# 03_-_Power_NDP_BLE_and_LRA.net
KiCad netlist of a schematic drawn in Altium Designer
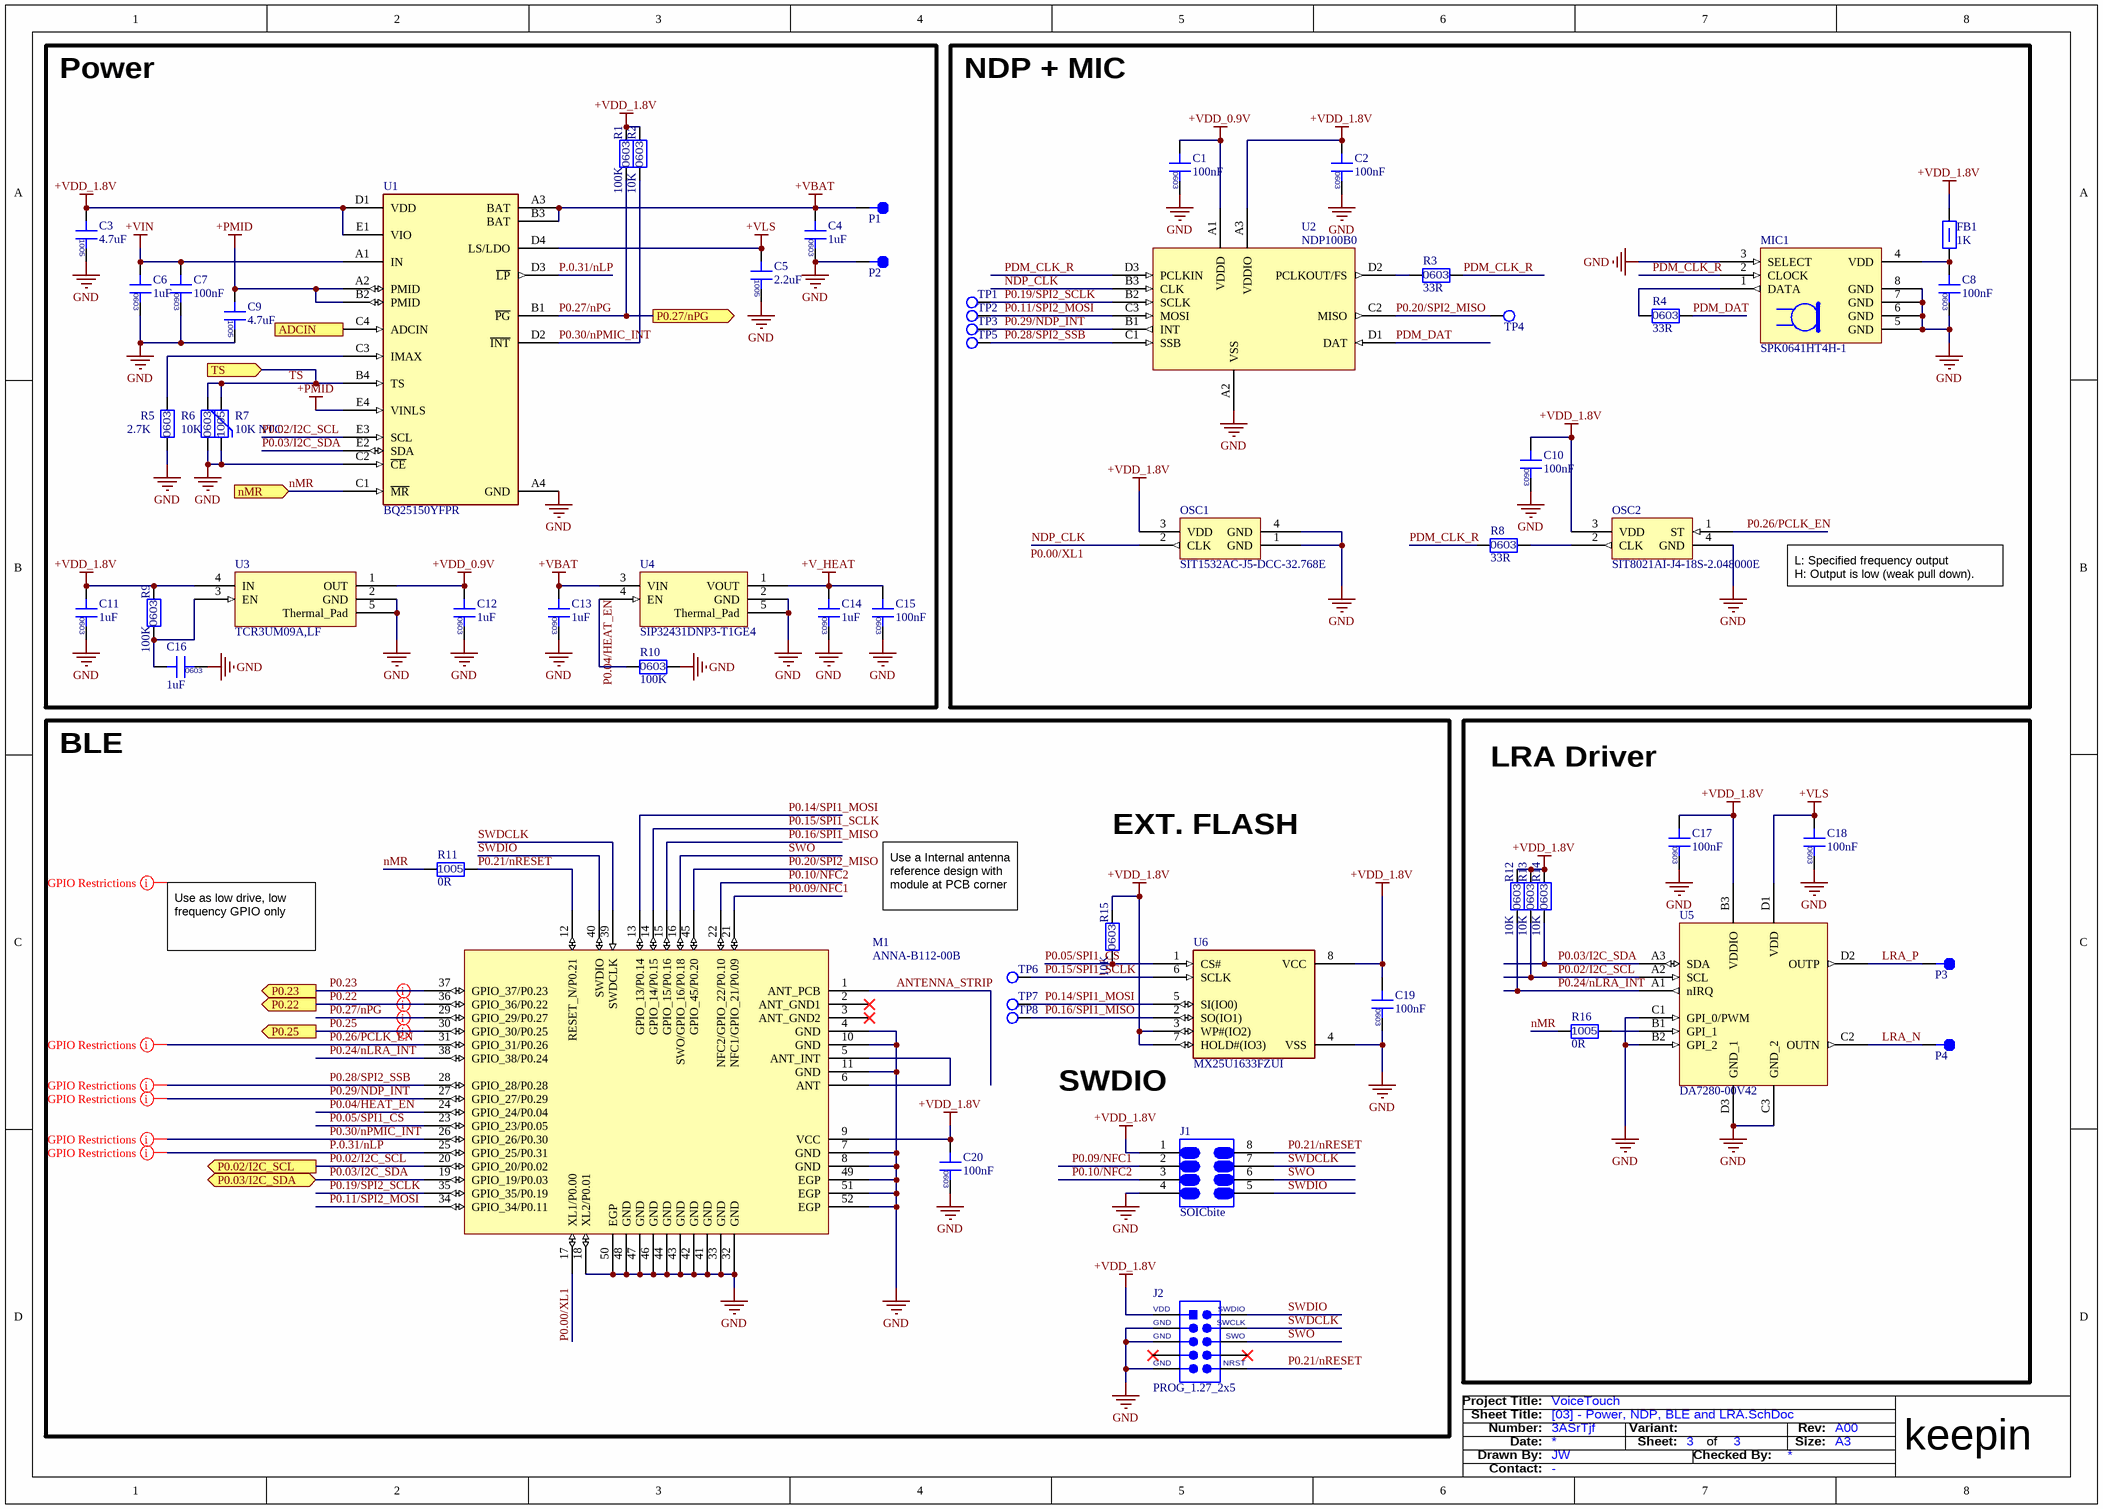
[diagram p0: [03] - Power, NDP, BLE and LRA.SchDoc]

(export (version "E")
  (design (tool "Eeschema 10.0.6"))
  (components
    (comp (ref "C1")
      (value "100nF")
      (footprint "CAPC0603X03N")
      (description "CAP CER 0.1UF 16V X7S 0201")
      (fields
        (field (name "MANUFACTURER") "Murata")
        (field (name "MANUFACTURER PART NUMBER") "GRM033C71C104ME14D")
      )
      (libsource (lib "Schlib-master") (part "GRM033C71C104ME14D"))
    )
    (comp (ref "C2")
      (value "100nF")
      (footprint "CAPC0603X03N")
      (description "CAP CER 0.1UF 16V X7S 0201")
      (fields
        (field (name "MANUFACTURER") "Murata")
        (field (name "MANUFACTURER PART NUMBER") "GRM033C71C104ME14D")
      )
      (libsource (lib "Schlib-master") (part "GRM033C71C104ME14D"))
    )
    (comp (ref "C3")
      (value "4.7uF")
      (footprint "CAPC1005X06N")
      (description "CAP CER 4.7UF 16V X5R 0402")
      (fields (field (name "TOLERANCE") "20%") (field (name "MANUFACTURER") "Samsung"))
      (libsource (lib "Schlib-master") (part "CL05A475MO5NUNC"))
    )
    (comp (ref "C4")
      (value "1uF")
      (footprint "CAPC0603X03N")
      (description "CAP CER 1UF 16V X5R 0201")
      (fields
        (field (name "MANUFACTURER") "Samsung")
        (field (name "MANUFACTURER PART NUMBER") "CL03A105MO3NRNH")
      )
      (libsource (lib "Schlib-master") (part "CL03A105MO3NRNH"))
    )
    (comp (ref "C5")
      (value "2.2uF")
      (footprint "CAPC1005X06N")
      (description "CAP CER 2.2UF 10V X5R 0402")
      (fields
        (field (name "MANUFACTURER") "Samsung")
        (field (name "MANUFACTURER PART NUMBER") "CL05A225KP7NSB8")
      )
      (libsource (lib "Schlib-master") (part "CL05A225KP7NSB8"))
    )
    (comp (ref "C6")
      (value "1uF")
      (footprint "CAPC0603X03N")
      (description "CAP CER 1UF 16V X5R 0201")
      (fields
        (field (name "MANUFACTURER") "Samsung")
        (field (name "MANUFACTURER PART NUMBER") "CL03A105MO3NRNH")
      )
      (libsource (lib "Schlib-master") (part "CL03A105MO3NRNH"))
    )
    (comp (ref "C7")
      (value "100nF")
      (footprint "CAPC0603X03N")
      (description "CAP CER 0.1UF 16V X7S 0201")
      (fields
        (field (name "MANUFACTURER") "Murata")
        (field (name "MANUFACTURER PART NUMBER") "GRM033C71C104ME14D")
      )
      (libsource (lib "Schlib-master") (part "GRM033C71C104ME14D"))
    )
    (comp (ref "C8")
      (value "100nF")
      (footprint "CAPC0603X03N")
      (description "CAP CER 0.1UF 16V X7S 0201")
      (fields
        (field (name "MANUFACTURER") "Murata")
        (field (name "MANUFACTURER PART NUMBER") "GRM033C71C104ME14D")
      )
      (libsource (lib "Schlib-master") (part "GRM033C71C104ME14D"))
    )
    (comp (ref "C9")
      (value "4.7uF")
      (footprint "CAPC1005X06N")
      (description "CAP CER 4.7UF 16V X5R 0402")
      (fields (field (name "TOLERANCE") "20%") (field (name "MANUFACTURER") "Samsung"))
      (libsource (lib "Schlib-master") (part "CL05A475MO5NUNC"))
    )
    (comp (ref "C10")
      (value "100nF")
      (footprint "CAPC0603X03N")
      (description "CAP CER 0.1UF 16V X7S 0201")
      (fields
        (field (name "MANUFACTURER") "Murata")
        (field (name "MANUFACTURER PART NUMBER") "GRM033C71C104ME14D")
      )
      (libsource (lib "Schlib-master") (part "GRM033C71C104ME14D"))
    )
    (comp (ref "C11")
      (value "1uF")
      (footprint "CAPC0603X03N")
      (description "CAP CER 1UF 16V X5R 0201")
      (fields
        (field (name "MANUFACTURER") "Samsung")
        (field (name "MANUFACTURER PART NUMBER") "CL03A105MO3NRNH")
      )
      (libsource (lib "Schlib-master") (part "CL03A105MO3NRNH"))
    )
    (comp (ref "C12")
      (value "1uF")
      (footprint "CAPC0603X03N")
      (description "CAP CER 1UF 16V X5R 0201")
      (fields
        (field (name "MANUFACTURER") "Samsung")
        (field (name "MANUFACTURER PART NUMBER") "CL03A105MO3NRNH")
      )
      (libsource (lib "Schlib-master") (part "CL03A105MO3NRNH"))
    )
    (comp (ref "C13")
      (value "1uF")
      (footprint "CAPC0603X03N")
      (description "CAP CER 1UF 16V X5R 0201")
      (fields
        (field (name "MANUFACTURER") "Samsung")
        (field (name "MANUFACTURER PART NUMBER") "CL03A105MO3NRNH")
      )
      (libsource (lib "Schlib-master") (part "CL03A105MO3NRNH"))
    )
    (comp (ref "C14")
      (value "1uF")
      (footprint "CAPC0603X03N")
      (description "CAP CER 1UF 16V X5R 0201")
      (fields
        (field (name "MANUFACTURER") "Samsung")
        (field (name "MANUFACTURER PART NUMBER") "CL03A105MO3NRNH")
      )
      (libsource (lib "Schlib-master") (part "CL03A105MO3NRNH"))
    )
    (comp (ref "C15")
      (value "100nF")
      (footprint "CAPC0603X03N")
      (description "CAP CER 0.1UF 16V X7S 0201")
      (fields
        (field (name "MANUFACTURER") "Murata")
        (field (name "MANUFACTURER PART NUMBER") "GRM033C71C104ME14D")
      )
      (libsource (lib "Schlib-master") (part "GRM033C71C104ME14D"))
    )
    (comp (ref "C16")
      (value "1uF")
      (footprint "CAPC0603X03N")
      (description "CAP CER 1UF 16V X5R 0201")
      (fields
        (field (name "MANUFACTURER") "Samsung")
        (field (name "MANUFACTURER PART NUMBER") "CL03A105MO3NRNH")
      )
      (libsource (lib "Schlib-master") (part "CL03A105MO3NRNH"))
    )
    (comp (ref "C17")
      (value "100nF")
      (footprint "CAPC0603X03N")
      (description "CAP CER 0.1UF 16V X7S 0201")
      (fields
        (field (name "MANUFACTURER") "Murata")
        (field (name "MANUFACTURER PART NUMBER") "GRM033C71C104ME14D")
      )
      (libsource (lib "Schlib-master") (part "GRM033C71C104ME14D"))
    )
    (comp (ref "C18")
      (value "100nF")
      (footprint "CAPC0603X03N")
      (description "CAP CER 0.1UF 16V X7S 0201")
      (fields
        (field (name "MANUFACTURER") "Murata")
        (field (name "MANUFACTURER PART NUMBER") "GRM033C71C104ME14D")
      )
      (libsource (lib "Schlib-master") (part "GRM033C71C104ME14D"))
    )
    (comp (ref "C19")
      (value "100nF")
      (footprint "CAPC0603X03N")
      (description "CAP CER 0.1UF 16V X7S 0201")
      (fields
        (field (name "MANUFACTURER") "Murata")
        (field (name "MANUFACTURER PART NUMBER") "GRM033C71C104ME14D")
      )
      (libsource (lib "Schlib-master") (part "GRM033C71C104ME14D"))
    )
    (comp (ref "C20")
      (value "100nF")
      (footprint "CAPC0603X03N")
      (description "CAP CER 0.1UF 16V X7S 0201")
      (fields
        (field (name "MANUFACTURER") "Murata")
        (field (name "MANUFACTURER PART NUMBER") "GRM033C71C104ME14D")
      )
      (libsource (lib "Schlib-master") (part "GRM033C71C104ME14D"))
    )
    (comp (ref "FB1")
      (value "1K")
      (footprint "INDC1005X05N")
      (description "FERRITE BEAD 1 KOHM 0402 1LN")
      (fields (field (name "TOLERANCE") "25%") (field (name "MANUFACTURER") "Murata"))
      (libsource (lib "Schlib") (part "BLM15HG102SN1D"))
    )
    (comp (ref "J1")
      (value "SOICbite")
      (footprint "SOICBITE")
      (fields (field (name "MANUFACTURER") "SimonMerrett"))
      (libsource (lib "Schlib-master") (part "SOICbite"))
    )
    (comp (ref "J2")
      (value "PROG_1.27_2x5")
      (footprint "2x5_HEADER_1.27_SMD")
      (description "CONN HEADER SMD 10POS 1.27MM")
      (fields
        (field (name "MANUFACTURER") "Amphenol FCI")
        (field (name "MANUFACTURER PART NUMBER") "20021121-00010C4LF")
      )
      (libsource (lib "Schlib-master") (part "PROG_1.27_2x5"))
    )
    (comp (ref "M1")
      (value "ANNA-B112-00B")
      (footprint "ANNA-B112")
      (description "RX TXRX MODULE BLUETOOTH SMD")
      (fields (field (name "MANUFACTURER") "u-blox"))
      (libsource (lib "Schlib-master") (part "ANNA-B112-00B"))
    )
    (comp (ref "MIC1")
      (value "SPK0641HT4H-1")
      (footprint "MIC_SPK0838HT4H-1")
      (description "RAMIS MIC MULTIMODE DGT TOP PORT")
      (fields (field (name "MANUFACTURER") "Knowles"))
      (libsource (lib "Schlib") (part "SPK0641HT4H-1"))
    )
    (comp (ref "OSC1")
      (value "SIT1532AC-J5-DCC-32.768E")
      (footprint "SIT1532")
      (description "MEMS OSC XO 32.7680KHZ LVCMOS")
      (fields (field (name "MANUFACTURER") "SiTime"))
      (libsource (lib "Schlib-master") (part "SIT1532AC-J5-DCC-32.768E"))
    )
    (comp (ref "OSC2")
      (value "SIT8021AI-J4-18S-2.048000E")
      (footprint "SIT1532")
      (description "MEMS OSC XO 2.0480MHZ LVCMOS SMD")
      (fields (field (name "MANUFACTURER") "SiTime"))
      (libsource (lib "Schlib-master") (part "SIT8021AI-J4-18S-2.048000E"))
    )
    (comp (ref "P1")
      (value "1x1_Octagonal_1.27")
      (footprint "1x1_OCTAGONAL_1.27")
      (libsource (lib "Schlib-master") (part "1x1_Octagonal_1.27"))
    )
    (comp (ref "P2")
      (value "1x1_Octagonal_1.27")
      (footprint "1x1_OCTAGONAL_1.27")
      (libsource (lib "Schlib-master") (part "1x1_Octagonal_1.27"))
    )
    (comp (ref "P3")
      (value "1x1_Octagonal_1.27")
      (footprint "1x1_OCTAGONAL_1.27")
      (libsource (lib "Schlib-master") (part "1x1_Octagonal_1.27"))
    )
    (comp (ref "P4")
      (value "1x1_Octagonal_1.27")
      (footprint "1x1_OCTAGONAL_1.27")
      (libsource (lib "Schlib-master") (part "1x1_Octagonal_1.27"))
    )
    (comp (ref "R1")
      (value "100K")
      (footprint "RESC0603X02N")
      (description "RES SMD 100K OHM 5% 1/20W 0201")
      (fields
        (field (name "MANUFACTURER") "Yageo")
        (field (name "MANUFACTURER PART NUMBER") "RC0201JR-07100KL")
      )
      (libsource (lib "Schlib-master") (part "RC0201JR-07100KL"))
    )
    (comp (ref "R2")
      (value "10K")
      (footprint "RESC0603X02N")
      (description "RES SMD 10K OHM 1% 1/20W 0201")
      (fields
        (field (name "MANUFACTURER") "Yageo")
        (field (name "MANUFACTURER PART NUMBER") "RC0201FR-0710KL")
      )
      (libsource (lib "Schlib-master") (part "RC0201FR-0710KL"))
    )
    (comp (ref "R3")
      (value "33R")
      (footprint "RESC0603X02N")
      (description "RES SMD 33 OHM 1% 1/20W 0201")
      (fields
        (field (name "MANUFACTURER") "Yageo")
        (field (name "MANUFACTURER PART NUMBER") "RC0201FR-0733RL")
      )
      (libsource (lib "Schlib-master") (part "RC0201FR-0733RL"))
    )
    (comp (ref "R4")
      (value "33R")
      (footprint "RESC0603X02N")
      (description "RES SMD 33 OHM 1% 1/20W 0201")
      (fields
        (field (name "MANUFACTURER") "Yageo")
        (field (name "MANUFACTURER PART NUMBER") "RC0201FR-0733RL")
      )
      (libsource (lib "Schlib-master") (part "RC0201FR-0733RL"))
    )
    (comp (ref "R5")
      (value "2.7K")
      (footprint "RESC0603X02N")
      (description "RES SMD 2.7K OHM 1% 1/20W 0201")
      (fields
        (field (name "MANUFACTURER") "Yageo")
        (field (name "MANUFACTURER PART NUMBER") "RC0201FR-072K7L")
      )
      (libsource (lib "Schlib-master") (part "RC0201FR-072K7L"))
    )
    (comp (ref "R6")
      (value "10K")
      (footprint "RESC0603X02N")
      (description "RES SMD 10K OHM 1% 1/20W 0201")
      (fields
        (field (name "MANUFACTURER") "Yageo")
        (field (name "MANUFACTURER PART NUMBER") "RC0201FR-0710KL")
      )
      (libsource (lib "Schlib-master") (part "RC0201FR-0710KL"))
    )
    (comp (ref "R7")
      (value "10K NTC")
      (footprint "NTC1005X05N")
      (description "THERMISTOR NTC 10KOHM 3380K 0402")
      (fields (field (name "TOLERANCE") "5%") (field (name "MANUFACTURER") "Murata"))
      (libsource (lib "Schlib-master") (part "NCP15XH103J03RC"))
    )
    (comp (ref "R8")
      (value "33R")
      (footprint "RESC0603X02N")
      (description "RES SMD 33 OHM 1% 1/20W 0201")
      (fields
        (field (name "MANUFACTURER") "Yageo")
        (field (name "MANUFACTURER PART NUMBER") "RC0201FR-0733RL")
      )
      (libsource (lib "Schlib-master") (part "RC0201FR-0733RL"))
    )
    (comp (ref "R9")
      (value "100K")
      (footprint "RESC0603X02N")
      (description "RES SMD 100K OHM 5% 1/20W 0201")
      (fields
        (field (name "MANUFACTURER") "Yageo")
        (field (name "MANUFACTURER PART NUMBER") "RC0201JR-07100KL")
      )
      (libsource (lib "Schlib-master") (part "RC0201JR-07100KL"))
    )
    (comp (ref "R10")
      (value "100K")
      (footprint "RESC0603X02N")
      (description "RES SMD 100K OHM 5% 1/20W 0201")
      (fields
        (field (name "MANUFACTURER") "Yageo")
        (field (name "MANUFACTURER PART NUMBER") "RC0201JR-07100KL")
      )
      (libsource (lib "") (part "RC0201JR-07100KL_1"))
    )
    (comp (ref "R11")
      (value "0R")
      (footprint "RESC1005X04N")
      (description "RES SMD 0 OHM JUMPER 1/16W 0402")
      (fields
        (field (name "MANUFACTURER") "Yageo")
        (field (name "MANUFACTURER PART NUMBER") "RC0402JR-070RL")
      )
      (libsource (lib "Schlib-master") (part "RC0402JR-070RL"))
    )
    (comp (ref "R12")
      (value "10K")
      (footprint "RESC0603X02N")
      (description "RES SMD 10K OHM 1% 1/20W 0201")
      (fields
        (field (name "MANUFACTURER") "Yageo")
        (field (name "MANUFACTURER PART NUMBER") "RC0201FR-0710KL")
      )
      (libsource (lib "Schlib-master") (part "RC0201FR-0710KL"))
    )
    (comp (ref "R13")
      (value "10K")
      (footprint "RESC0603X02N")
      (description "RES SMD 10K OHM 1% 1/20W 0201")
      (fields
        (field (name "MANUFACTURER") "Yageo")
        (field (name "MANUFACTURER PART NUMBER") "RC0201FR-0710KL")
      )
      (libsource (lib "Schlib-master") (part "RC0201FR-0710KL"))
    )
    (comp (ref "R14")
      (value "10K")
      (footprint "RESC0603X02N")
      (description "RES SMD 10K OHM 1% 1/20W 0201")
      (fields
        (field (name "MANUFACTURER") "Yageo")
        (field (name "MANUFACTURER PART NUMBER") "RC0201FR-0710KL")
      )
      (libsource (lib "Schlib-master") (part "RC0201FR-0710KL"))
    )
    (comp (ref "R15")
      (value "10K")
      (footprint "RESC0603X02N")
      (description "RES SMD 10K OHM 1% 1/20W 0201")
      (fields
        (field (name "MANUFACTURER") "Yageo")
        (field (name "MANUFACTURER PART NUMBER") "RC0201FR-0710KL")
      )
      (libsource (lib "Schlib-master") (part "RC0201FR-0710KL"))
    )
    (comp (ref "R16")
      (value "0R")
      (footprint "RESC1005X04N")
      (description "RES SMD 0 OHM JUMPER 1/16W 0402")
      (fields
        (field (name "MANUFACTURER") "Yageo")
        (field (name "MANUFACTURER PART NUMBER") "RC0402JR-070RL")
      )
      (libsource (lib "Schlib-master") (part "RC0402JR-070RL"))
    )
    (comp (ref "TP1")
      (value "TESTPOINT")
      (footprint "TESTPOINT_0.5mm")
      (description "TESTPOINT PAD")
      (libsource (lib "Schlib-master") (part "TESTPOINT"))
    )
    (comp (ref "TP2")
      (value "TESTPOINT")
      (footprint "TESTPOINT_0.5mm")
      (description "TESTPOINT PAD")
      (libsource (lib "Schlib-master") (part "TESTPOINT"))
    )
    (comp (ref "TP3")
      (value "TESTPOINT")
      (footprint "TESTPOINT_0.5mm")
      (description "TESTPOINT PAD")
      (libsource (lib "Schlib-master") (part "TESTPOINT"))
    )
    (comp (ref "TP4")
      (value "TESTPOINT")
      (footprint "TESTPOINT_0.5mm")
      (description "TESTPOINT PAD")
      (libsource (lib "Schlib-master") (part "TESTPOINT"))
    )
    (comp (ref "TP5")
      (value "TESTPOINT")
      (footprint "TESTPOINT_0.5mm")
      (description "TESTPOINT PAD")
      (libsource (lib "Schlib-master") (part "TESTPOINT"))
    )
    (comp (ref "TP6")
      (value "TESTPOINT")
      (footprint "TESTPOINT_0.5mm")
      (description "TESTPOINT PAD")
      (libsource (lib "Schlib-master") (part "TESTPOINT"))
    )
    (comp (ref "TP7")
      (value "TESTPOINT")
      (footprint "TESTPOINT_0.5mm")
      (description "TESTPOINT PAD")
      (libsource (lib "Schlib-master") (part "TESTPOINT"))
    )
    (comp (ref "TP8")
      (value "TESTPOINT")
      (footprint "TESTPOINT_0.5mm")
      (description "TESTPOINT PAD")
      (libsource (lib "Schlib-master") (part "TESTPOINT"))
    )
    (comp (ref "U1")
      (value "BQ25150YFPR")
      (footprint "YFP0020ACAC")
      (description "LOW IQ LINEAR BATTERY CHARGE MAN")
      (fields (field (name "MANUFACTURER") "Texas Instruments"))
      (libsource (lib "Schlib-master") (part "BQ25150YFPR"))
    )
    (comp (ref "U2")
      (value "NDP100B0")
      (footprint "NDP100B0_BGA12C40P3X4_139X176X55")
      (description "IC NDP 32BIT 112KB SRAM WLBGA")
      (fields (field (name "MANUFACTURER") "SYNTIANT"))
      (libsource (lib "Schlib-master") (part "NDP100B0"))
    )
    (comp (ref "U3")
      (value "TCR3UM09A,LF")
      (footprint "DQN-4")
      (description "IC REG LINEAR 0.9V 300MA 4DFN")
      (fields (field (name "MANUFACTURER") "Toshiba"))
      (libsource (lib "Schlib-master") (part "TCR3UM09A,LF"))
    )
    (comp (ref "U4")
      (value "SIP32431DNP3-T1GE4")
      (footprint "SON50P160X60_HS-5N")
      (description "IC PWR SWITCH P-CHAN 1:1 4TDFN")
      (fields (field (name "MANUFACTURER") "Vishay Siliconix"))
      (libsource (lib "Schlib-master") (part "SIP32431DNP3-T1GE4"))
    )
    (comp (ref "U5")
      (value "DA7280-00V42")
      (footprint "BGA12C40P3X4_135X175X57")
      (description "LRA/ERM HAPTIC DRIVER WLCSP12")
      (fields (field (name "MANUFACTURER") "Dialog Semiconductor"))
      (libsource (lib "Schlib-master") (part "DA7280-00V42"))
    )
    (comp (ref "U6")
      (value "MX25U1633FZUI")
      (footprint "USON8_3X2")
      (description "IC FLASH 16MBIT SPI/QUAD 8USON")
      (fields (field (name "MANUFACTURER") "Macronix"))
      (libsource (lib "Schlib-master") (part "MX25U1633FZUI"))
    )
  )
  (nets
    (net (code "1") (name "+PMID") (class "Default")
      (node (ref "C9") (pin "2") (pinfunction "2_2") (pintype "passive"))
      (node (ref "U1") (pin "A2") (pinfunction "PMID_A2") (pintype "bidirectional"))
      (node (ref "U1") (pin "B2") (pinfunction "PMID_B2") (pintype "bidirectional"))
      (node (ref "U1") (pin "E4") (pinfunction "VINLS_E4") (pintype "input"))
    )
    (net (code "2") (name "+VBAT") (class "Default")
      (node (ref "C13") (pin "2") (pinfunction "2_2") (pintype "passive"))
      (node (ref "C4") (pin "2") (pinfunction "2_2") (pintype "passive"))
      (node (ref "P1") (pin "1") (pinfunction "1_1") (pintype "passive"))
      (node (ref "U1") (pin "A3") (pinfunction "BAT_A3") (pintype "power_in"))
      (node (ref "U1") (pin "B3") (pinfunction "BAT_B3") (pintype "power_in"))
      (node (ref "U4") (pin "3") (pinfunction "VIN_3") (pintype "power_in"))
    )
    (net (code "3") (name "+VDD_0.9V") (class "Default")
      (node (ref "C1") (pin "2") (pinfunction "2_2") (pintype "passive"))
      (node (ref "C12") (pin "2") (pinfunction "2_2") (pintype "passive"))
      (node (ref "U2") (pin "A1") (pinfunction "VDDD_A1") (pintype "power_in"))
      (node (ref "U3") (pin "1") (pinfunction "OUT_1") (pintype "power_in"))
    )
    (net (code "4") (name "+VDD_1.8V") (class "Default")
      (node (ref "C10") (pin "2") (pinfunction "2_2") (pintype "passive"))
      (node (ref "C11") (pin "2") (pinfunction "2_2") (pintype "passive"))
      (node (ref "C17") (pin "2") (pinfunction "2_2") (pintype "passive"))
      (node (ref "C19") (pin "2") (pinfunction "2_2") (pintype "passive"))
      (node (ref "C2") (pin "2") (pinfunction "2_2") (pintype "passive"))
      (node (ref "C20") (pin "2") (pinfunction "2_2") (pintype "passive"))
      (node (ref "C3") (pin "2") (pinfunction "2_2") (pintype "passive"))
      (node (ref "FB1") (pin "1") (pinfunction "1_1") (pintype "passive"))
      (node (ref "J1") (pin "1") (pinfunction "1_1") (pintype "passive"))
      (node (ref "J2") (pin "1") (pinfunction "1_1") (pintype "passive"))
      (node (ref "M1") (pin "9") (pinfunction "VCC_9") (pintype "power_in"))
      (node (ref "OSC1") (pin "3") (pinfunction "VDD_3") (pintype "power_in"))
      (node (ref "OSC2") (pin "3") (pinfunction "VDD_3") (pintype "power_in"))
      (node (ref "R1") (pin "2") (pinfunction "2_2") (pintype "passive"))
      (node (ref "R12") (pin "2") (pinfunction "2_2") (pintype "passive"))
      (node (ref "R13") (pin "2") (pinfunction "2_2") (pintype "passive"))
      (node (ref "R14") (pin "2") (pinfunction "2_2") (pintype "passive"))
      (node (ref "R15") (pin "2") (pinfunction "2_2") (pintype "passive"))
      (node (ref "R2") (pin "2") (pinfunction "2_2") (pintype "passive"))
      (node (ref "R9") (pin "2") (pinfunction "2_2") (pintype "passive"))
      (node (ref "U1") (pin "D1") (pinfunction "VDD_D1") (pintype "power_in"))
      (node (ref "U1") (pin "E1") (pinfunction "VIO_E1") (pintype "power_in"))
      (node (ref "U2") (pin "A3") (pinfunction "VDDIO_A3") (pintype "power_in"))
      (node (ref "U3") (pin "4") (pinfunction "IN_4") (pintype "power_in"))
      (node (ref "U5") (pin "B3") (pinfunction "VDDIO_B3") (pintype "power_in"))
      (node (ref "U6") (pin "3") (pinfunction "WP#(IO2)_3") (pintype "bidirectional"))
      (node (ref "U6") (pin "7") (pinfunction "HOLD#(IO3)_7") (pintype "bidirectional"))
      (node (ref "U6") (pin "8") (pinfunction "VCC_8") (pintype "power_in"))
    )
    (net (code "5") (name "+VIN") (class "Default")
      (node (ref "C6") (pin "2") (pinfunction "2_2") (pintype "passive"))
      (node (ref "C7") (pin "2") (pinfunction "2_2") (pintype "passive"))
      (node (ref "U1") (pin "A1") (pinfunction "IN_A1") (pintype "power_in"))
    )
    (net (code "6") (name "+VLS") (class "Default")
      (node (ref "C18") (pin "2") (pinfunction "2_2") (pintype "passive"))
      (node (ref "C5") (pin "2") (pinfunction "2_2") (pintype "passive"))
      (node (ref "U1") (pin "D4") (pinfunction "LS/LDO_D4") (pintype "power_in"))
      (node (ref "U5") (pin "D1") (pinfunction "VDD_D1") (pintype "power_in"))
    )
    (net (code "7") (name "+V_HEAT") (class "Default")
      (node (ref "C14") (pin "2") (pinfunction "2_2") (pintype "passive"))
      (node (ref "C15") (pin "2") (pinfunction "2_2") (pintype "passive"))
      (node (ref "U4") (pin "1") (pinfunction "VOUT_1") (pintype "power_in"))
    )
    (net (code "8") (name "/ADCIN") (class "Default")
      (node (ref "U1") (pin "C4") (pinfunction "ADCIN_C4") (pintype "input"))
    )
    (net (code "9") (name "/ANTENNA_STRIP") (class "Default")
      (node (ref "M1") (pin "1") (pinfunction "ANT_PCB_1") (pintype "passive"))
    )
    (net (code "10") (name "/LRA_N") (class "Default")
      (node (ref "P4") (pin "1") (pinfunction "1_1") (pintype "passive"))
      (node (ref "U5") (pin "C2") (pinfunction "OUTN_C2") (pintype "output"))
    )
    (net (code "11") (name "/LRA_P") (class "Default")
      (node (ref "P3") (pin "1") (pinfunction "1_1") (pintype "passive"))
      (node (ref "U5") (pin "D2") (pinfunction "OUTP_D2") (pintype "output"))
    )
    (net (code "12") (name "/NDP_CLK") (class "Default")
      (node (ref "M1") (pin "17") (pinfunction "XL1/P0.00_17") (pintype "bidirectional"))
      (node (ref "OSC1") (pin "2") (pinfunction "CLK_2") (pintype "output"))
      (node (ref "U2") (pin "B3") (pinfunction "CLK_B3") (pintype "input"))
    )
    (net (code "13") (name "/P.0.31{slash}nLP") (class "Default")
      (node (ref "M1") (pin "25") (pinfunction "GPIO_25/P0.31_25") (pintype "bidirectional"))
      (node (ref "U1") (pin "D3") (pinfunction "~{LP}_D3") (pintype "output"))
    )
    (net (code "14") (name "/P0.02{slash}I2C_SCL") (class "Default")
      (node (ref "M1") (pin "20") (pinfunction "GPIO_20/P0.02_20") (pintype "bidirectional"))
      (node (ref "R13") (pin "1") (pinfunction "1_1") (pintype "passive"))
      (node (ref "U1") (pin "E3") (pinfunction "SCL_E3") (pintype "input"))
      (node (ref "U5") (pin "A2") (pinfunction "SCL_A2") (pintype "input"))
    )
    (net (code "15") (name "/P0.03{slash}I2C_SDA") (class "Default")
      (node (ref "M1") (pin "19") (pinfunction "GPIO_19/P0.03_19") (pintype "bidirectional"))
      (node (ref "R14") (pin "1") (pinfunction "1_1") (pintype "passive"))
      (node (ref "U1") (pin "E2") (pinfunction "SDA_E2") (pintype "bidirectional"))
      (node (ref "U5") (pin "A3") (pinfunction "SDA_A3") (pintype "bidirectional"))
    )
    (net (code "16") (name "/P0.04{slash}HEAT_EN") (class "Default")
      (node (ref "M1") (pin "24") (pinfunction "GPIO_24/P0.04_24") (pintype "bidirectional"))
      (node (ref "R10") (pin "1") (pinfunction "1_1") (pintype "passive"))
      (node (ref "U4") (pin "4") (pinfunction "EN_4") (pintype "input"))
    )
    (net (code "17") (name "/P0.05{slash}SPI1_CS") (class "Default")
      (node (ref "M1") (pin "23") (pinfunction "GPIO_23/P0.05_23") (pintype "bidirectional"))
      (node (ref "R15") (pin "1") (pinfunction "1_1") (pintype "passive"))
      (node (ref "U6") (pin "1") (pinfunction "CS#_1") (pintype "input"))
    )
    (net (code "18") (name "/P0.09{slash}NFC1") (class "Default")
      (node (ref "J1") (pin "2") (pinfunction "2_2") (pintype "passive"))
      (node (ref "M1") (pin "21") (pinfunction "NFC1/GPIO_21/P0.09_21") (pintype "bidirectional"))
    )
    (net (code "19") (name "/P0.10{slash}NFC2") (class "Default")
      (node (ref "J1") (pin "3") (pinfunction "3_3") (pintype "passive"))
      (node (ref "M1") (pin "22") (pinfunction "NFC2/GPIO_22/P0.10_22") (pintype "bidirectional"))
    )
    (net (code "20") (name "/P0.11{slash}SPI2_MOSI") (class "Default")
      (node (ref "M1") (pin "34") (pinfunction "GPIO_34/P0.11_34") (pintype "bidirectional"))
      (node (ref "TP2") (pin "1") (pinfunction "1_1") (pintype "passive"))
      (node (ref "U2") (pin "C3") (pinfunction "MOSI_C3") (pintype "input"))
    )
    (net (code "21") (name "/P0.14{slash}SPI1_MOSI") (class "Default")
      (node (ref "M1") (pin "13") (pinfunction "GPIO_13/P0.14_13") (pintype "bidirectional"))
      (node (ref "TP7") (pin "1") (pinfunction "1_1") (pintype "passive"))
      (node (ref "U6") (pin "5") (pinfunction "SI(IO0)_5") (pintype "bidirectional"))
    )
    (net (code "22") (name "/P0.15{slash}SPI1_SCLK") (class "Default")
      (node (ref "M1") (pin "14") (pinfunction "GPIO_14/P0.15_14") (pintype "bidirectional"))
      (node (ref "TP6") (pin "1") (pinfunction "1_1") (pintype "passive"))
      (node (ref "U6") (pin "6") (pinfunction "SCLK_6") (pintype "input"))
    )
    (net (code "23") (name "/P0.16{slash}SPI1_MISO") (class "Default")
      (node (ref "M1") (pin "15") (pinfunction "GPIO_15/P0.16_15") (pintype "bidirectional"))
      (node (ref "TP8") (pin "1") (pinfunction "1_1") (pintype "passive"))
      (node (ref "U6") (pin "2") (pinfunction "SO(IO1)_2") (pintype "bidirectional"))
    )
    (net (code "24") (name "/P0.19{slash}SPI2_SCLK") (class "Default")
      (node (ref "M1") (pin "35") (pinfunction "GPIO_35/P0.19_35") (pintype "bidirectional"))
      (node (ref "TP1") (pin "1") (pinfunction "1_1") (pintype "passive"))
      (node (ref "U2") (pin "B2") (pinfunction "SCLK_B2") (pintype "input"))
    )
    (net (code "25") (name "/P0.20{slash}SPI2_MISO") (class "Default")
      (node (ref "M1") (pin "45") (pinfunction "GPIO_45/P0.20_45") (pintype "bidirectional"))
      (node (ref "TP4") (pin "1") (pinfunction "1_1") (pintype "passive"))
      (node (ref "U2") (pin "C2") (pinfunction "MISO_C2") (pintype "output"))
    )
    (net (code "26") (name "/P0.21{slash}nRESET") (class "Default")
      (node (ref "J1") (pin "8") (pinfunction "8_8") (pintype "passive"))
      (node (ref "J2") (pin "10") (pinfunction "10_10") (pintype "passive"))
      (node (ref "M1") (pin "12") (pinfunction "RESET_N/P0.21_12") (pintype "bidirectional"))
      (node (ref "R11") (pin "2") (pinfunction "2_2") (pintype "passive"))
    )
    (net (code "27") (name "/P0.22") (class "Default")
      (node (ref "M1") (pin "36") (pinfunction "GPIO_36/P0.22_36") (pintype "bidirectional"))
    )
    (net (code "28") (name "/P0.23") (class "Default")
      (node (ref "M1") (pin "37") (pinfunction "GPIO_37/P0.23_37") (pintype "bidirectional"))
    )
    (net (code "29") (name "/P0.24{slash}nLRA_INT") (class "Default")
      (node (ref "M1") (pin "38") (pinfunction "GPIO_38/P0.24_38") (pintype "bidirectional"))
      (node (ref "R12") (pin "1") (pinfunction "1_1") (pintype "passive"))
      (node (ref "U5") (pin "A1") (pinfunction "nIRQ_A1") (pintype "output"))
    )
    (net (code "30") (name "/P0.25") (class "Default")
      (node (ref "M1") (pin "30") (pinfunction "GPIO_30/P0.25_30") (pintype "bidirectional"))
    )
    (net (code "31") (name "/P0.26{slash}PCLK_EN") (class "Default")
      (node (ref "M1") (pin "31") (pinfunction "GPIO_31/P0.26_31") (pintype "bidirectional"))
      (node (ref "OSC2") (pin "1") (pinfunction "ST_1") (pintype "input"))
    )
    (net (code "32") (name "/P0.27{slash}nPG") (class "Default")
      (node (ref "M1") (pin "29") (pinfunction "GPIO_29/P0.27_29") (pintype "bidirectional"))
      (node (ref "R1") (pin "1") (pinfunction "1_1") (pintype "passive"))
      (node (ref "U1") (pin "B1") (pinfunction "~{PG}_B1") (pintype "open_collector"))
    )
    (net (code "33") (name "/P0.28{slash}SPI2_SSB") (class "Default")
      (node (ref "M1") (pin "28") (pinfunction "GPIO_28/P0.28_28") (pintype "bidirectional"))
      (node (ref "TP5") (pin "1") (pinfunction "1_1") (pintype "passive"))
      (node (ref "U2") (pin "C1") (pinfunction "SSB_C1") (pintype "input"))
    )
    (net (code "34") (name "/P0.29{slash}NDP_INT") (class "Default")
      (node (ref "M1") (pin "27") (pinfunction "GPIO_27/P0.29_27") (pintype "bidirectional"))
      (node (ref "TP3") (pin "1") (pinfunction "1_1") (pintype "passive"))
      (node (ref "U2") (pin "B1") (pinfunction "INT_B1") (pintype "output"))
    )
    (net (code "35") (name "/P0.30{slash}nPMIC_INT") (class "Default")
      (node (ref "M1") (pin "26") (pinfunction "GPIO_26/P0.30_26") (pintype "bidirectional"))
      (node (ref "R2") (pin "1") (pinfunction "1_1") (pintype "passive"))
      (node (ref "U1") (pin "D2") (pinfunction "~{INT}_D2") (pintype "open_collector"))
    )
    (net (code "36") (name "/PDM_CLK_R") (class "Default")
      (node (ref "MIC1") (pin "2") (pinfunction "CLOCK_2") (pintype "input"))
      (node (ref "R3") (pin "2") (pinfunction "2_2") (pintype "passive"))
      (node (ref "R8") (pin "1") (pinfunction "1_1") (pintype "passive"))
      (node (ref "U2") (pin "D3") (pinfunction "PCLKIN_D3") (pintype "input"))
    )
    (net (code "37") (name "/PDM_DAT") (class "Default")
      (node (ref "R4") (pin "2") (pinfunction "2_2") (pintype "passive"))
      (node (ref "U2") (pin "D1") (pinfunction "DAT_D1") (pintype "input"))
    )
    (net (code "38") (name "/SWDCLK") (class "Default")
      (node (ref "J1") (pin "7") (pinfunction "7_7") (pintype "passive"))
      (node (ref "J2") (pin "4") (pinfunction "4_4") (pintype "passive"))
      (node (ref "M1") (pin "39") (pinfunction "SWDCLK_39") (pintype "input"))
    )
    (net (code "39") (name "/SWDIO") (class "Default")
      (node (ref "J1") (pin "5") (pinfunction "5_5") (pintype "passive"))
      (node (ref "J2") (pin "2") (pinfunction "2_2") (pintype "passive"))
      (node (ref "M1") (pin "40") (pinfunction "SWDIO_40") (pintype "bidirectional"))
    )
    (net (code "40") (name "/SWO") (class "Default")
      (node (ref "J1") (pin "6") (pinfunction "6_6") (pintype "passive"))
      (node (ref "J2") (pin "6") (pinfunction "6_6") (pintype "passive"))
      (node (ref "M1") (pin "16") (pinfunction "SWO/GPIO_16/P0.18_16") (pintype "bidirectional"))
    )
    (net (code "41") (name "/TS") (class "Default")
      (node (ref "R6") (pin "2") (pinfunction "2_2") (pintype "passive"))
      (node (ref "R7") (pin "2") (pinfunction "2_2") (pintype "passive"))
      (node (ref "U1") (pin "B4") (pinfunction "TS_B4") (pintype "input"))
    )
    (net (code "42") (name "/nMR") (class "Default")
      (node (ref "R11") (pin "1") (pinfunction "1_1") (pintype "passive"))
      (node (ref "R16") (pin "1") (pinfunction "1_1") (pintype "passive"))
      (node (ref "U1") (pin "C1") (pinfunction "~{MR}_C1") (pintype "input"))
    )
    (net (code "43") (name "GND") (class "Default")
      (node (ref "C1") (pin "1") (pinfunction "1_1") (pintype "passive"))
      (node (ref "C10") (pin "1") (pinfunction "1_1") (pintype "passive"))
      (node (ref "C11") (pin "1") (pinfunction "1_1") (pintype "passive"))
      (node (ref "C12") (pin "1") (pinfunction "1_1") (pintype "passive"))
      (node (ref "C13") (pin "1") (pinfunction "1_1") (pintype "passive"))
      (node (ref "C14") (pin "1") (pinfunction "1_1") (pintype "passive"))
      (node (ref "C15") (pin "1") (pinfunction "1_1") (pintype "passive"))
      (node (ref "C16") (pin "1") (pinfunction "1_1") (pintype "passive"))
      (node (ref "C17") (pin "1") (pinfunction "1_1") (pintype "passive"))
      (node (ref "C18") (pin "1") (pinfunction "1_1") (pintype "passive"))
      (node (ref "C19") (pin "1") (pinfunction "1_1") (pintype "passive"))
      (node (ref "C2") (pin "1") (pinfunction "1_1") (pintype "passive"))
      (node (ref "C20") (pin "1") (pinfunction "1_1") (pintype "passive"))
      (node (ref "C3") (pin "1") (pinfunction "1_1") (pintype "passive"))
      (node (ref "C4") (pin "1") (pinfunction "1_1") (pintype "passive"))
      (node (ref "C5") (pin "1") (pinfunction "1_1") (pintype "passive"))
      (node (ref "C6") (pin "1") (pinfunction "1_1") (pintype "passive"))
      (node (ref "C7") (pin "1") (pinfunction "1_1") (pintype "passive"))
      (node (ref "C8") (pin "1") (pinfunction "1_1") (pintype "passive"))
      (node (ref "C9") (pin "1") (pinfunction "1_1") (pintype "passive"))
      (node (ref "J1") (pin "4") (pinfunction "4_4") (pintype "passive"))
      (node (ref "J2") (pin "3") (pinfunction "3_3") (pintype "passive"))
      (node (ref "J2") (pin "5") (pinfunction "5_5") (pintype "passive"))
      (node (ref "J2") (pin "9") (pinfunction "9_9") (pintype "passive"))
      (node (ref "M1") (pin "10") (pinfunction "GND_10") (pintype "power_in"))
      (node (ref "M1") (pin "11") (pinfunction "GND_11") (pintype "power_in"))
      (node (ref "M1") (pin "18") (pinfunction "XL2/P0.01_18") (pintype "bidirectional"))
      (node (ref "M1") (pin "32") (pinfunction "GND_32") (pintype "power_in"))
      (node (ref "M1") (pin "33") (pinfunction "GND_33") (pintype "power_in"))
      (node (ref "M1") (pin "4") (pinfunction "GND_4") (pintype "power_in"))
      (node (ref "M1") (pin "41") (pinfunction "GND_41") (pintype "power_in"))
      (node (ref "M1") (pin "42") (pinfunction "GND_42") (pintype "power_in"))
      (node (ref "M1") (pin "43") (pinfunction "GND_43") (pintype "power_in"))
      (node (ref "M1") (pin "44") (pinfunction "GND_44") (pintype "power_in"))
      (node (ref "M1") (pin "46") (pinfunction "GND_46") (pintype "power_in"))
      (node (ref "M1") (pin "47") (pinfunction "GND_47") (pintype "power_in"))
      (node (ref "M1") (pin "48") (pinfunction "GND_48") (pintype "power_in"))
      (node (ref "M1") (pin "49") (pinfunction "EGP_49") (pintype "power_in"))
      (node (ref "M1") (pin "50") (pinfunction "EGP_50") (pintype "power_in"))
      (node (ref "M1") (pin "51") (pinfunction "EGP_51") (pintype "power_in"))
      (node (ref "M1") (pin "52") (pinfunction "EGP_52") (pintype "power_in"))
      (node (ref "M1") (pin "7") (pinfunction "GND_7") (pintype "power_in"))
      (node (ref "M1") (pin "8") (pinfunction "GND_8") (pintype "power_in"))
      (node (ref "MIC1") (pin "3") (pinfunction "SELECT_3") (pintype "input"))
      (node (ref "MIC1") (pin "5") (pinfunction "GND_5") (pintype "power_in"))
      (node (ref "MIC1") (pin "6") (pinfunction "GND_6") (pintype "power_in"))
      (node (ref "MIC1") (pin "7") (pinfunction "GND_7") (pintype "power_in"))
      (node (ref "MIC1") (pin "8") (pinfunction "GND_8") (pintype "power_in"))
      (node (ref "OSC1") (pin "1") (pinfunction "GND_1") (pintype "power_in"))
      (node (ref "OSC1") (pin "4") (pinfunction "GND_4") (pintype "power_in"))
      (node (ref "OSC2") (pin "4") (pinfunction "GND_4") (pintype "power_in"))
      (node (ref "P2") (pin "1") (pinfunction "1_1") (pintype "passive"))
      (node (ref "R10") (pin "2") (pinfunction "2_2") (pintype "passive"))
      (node (ref "R5") (pin "1") (pinfunction "1_1") (pintype "passive"))
      (node (ref "R6") (pin "1") (pinfunction "1_1") (pintype "passive"))
      (node (ref "R7") (pin "1") (pinfunction "1_1") (pintype "passive"))
      (node (ref "U1") (pin "A4") (pinfunction "GND_A4") (pintype "power_in"))
      (node (ref "U1") (pin "C2") (pinfunction "~{CE}_C2") (pintype "input"))
      (node (ref "U2") (pin "A2") (pinfunction "VSS_A2") (pintype "power_in"))
      (node (ref "U3") (pin "2") (pinfunction "GND_2") (pintype "power_in"))
      (node (ref "U3") (pin "5") (pinfunction "Thermal_Pad_5") (pintype "passive"))
      (node (ref "U4") (pin "2") (pinfunction "GND_2") (pintype "power_in"))
      (node (ref "U4") (pin "5") (pinfunction "Thermal_Pad_5") (pintype "power_in"))
      (node (ref "U5") (pin "B2") (pinfunction "GPI_2_B2") (pintype "input"))
      (node (ref "U5") (pin "C1") (pinfunction "GPI_0/PWM_C1") (pintype "input"))
      (node (ref "U5") (pin "C3") (pinfunction "GND_2_C3") (pintype "power_in"))
      (node (ref "U5") (pin "D3") (pinfunction "GND_1_D3") (pintype "power_in"))
      (node (ref "U6") (pin "4") (pinfunction "VSS_4") (pintype "power_in"))
    )
    (net (code "44") (name "Net-(M1-ANT)") (class "Default")
      (node (ref "M1") (pin "5") (pinfunction "ANT_INT_5") (pintype "passive"))
      (node (ref "M1") (pin "6") (pinfunction "ANT_6") (pintype "passive"))
    )
    (net (code "45") (name "Net-(MIC1-DATA)") (class "Default")
      (node (ref "MIC1") (pin "1") (pinfunction "DATA_1") (pintype "output"))
      (node (ref "R4") (pin "1") (pinfunction "1_1") (pintype "passive"))
    )
    (net (code "46") (name "Net-(MIC1-VDD)") (class "Default")
      (node (ref "C8") (pin "2") (pinfunction "2_2") (pintype "passive"))
      (node (ref "FB1") (pin "2") (pinfunction "2_2") (pintype "passive"))
      (node (ref "MIC1") (pin "4") (pinfunction "VDD_4") (pintype "power_in"))
    )
    (net (code "47") (name "Net-(OSC2-CLK)") (class "Default")
      (node (ref "OSC2") (pin "2") (pinfunction "CLK_2") (pintype "output"))
      (node (ref "R8") (pin "2") (pinfunction "2_2") (pintype "passive"))
    )
    (net (code "48") (name "Net-(U1-IMAX)") (class "Default")
      (node (ref "R5") (pin "2") (pinfunction "2_2") (pintype "passive"))
      (node (ref "U1") (pin "C3") (pinfunction "IMAX_C3") (pintype "input"))
    )
    (net (code "49") (name "Net-(U2-PCLKOUT{slash}FS)") (class "Default")
      (node (ref "R3") (pin "1") (pinfunction "1_1") (pintype "passive"))
      (node (ref "U2") (pin "D2") (pinfunction "PCLKOUT/FS_D2") (pintype "output"))
    )
    (net (code "50") (name "Net-(U3-EN)") (class "Default")
      (node (ref "C16") (pin "2") (pinfunction "2_2") (pintype "passive"))
      (node (ref "R9") (pin "1") (pinfunction "1_1") (pintype "passive"))
      (node (ref "U3") (pin "3") (pinfunction "EN_3") (pintype "input"))
    )
    (net (code "51") (name "Net-(U5-GPI_1)") (class "Default")
      (node (ref "R16") (pin "2") (pinfunction "2_2") (pintype "passive"))
      (node (ref "U5") (pin "B1") (pinfunction "GPI_1_B1") (pintype "input"))
    )
    (net (code "52") (name "unconnected-(J2-Pad7)") (class "Default")
      (node (ref "J2") (pin "7") (pinfunction "7_7") (pintype "passive+no_connect"))
    )
    (net (code "53") (name "unconnected-(J2-Pad8)") (class "Default")
      (node (ref "J2") (pin "8") (pinfunction "8_8") (pintype "passive+no_connect"))
    )
    (net (code "54") (name "unconnected-(M1-ANT_GND1-Pad2)") (class "Default")
      (node (ref "M1") (pin "2") (pinfunction "ANT_GND1_2") (pintype "passive+no_connect"))
    )
    (net (code "55") (name "unconnected-(M1-ANT_GND2-Pad3)") (class "Default")
      (node (ref "M1") (pin "3") (pinfunction "ANT_GND2_3") (pintype "passive+no_connect"))
    )
  )
)
